# FZZSHAP_REVISED.net
KiCad netlist of a schematic drawn in EAGLE
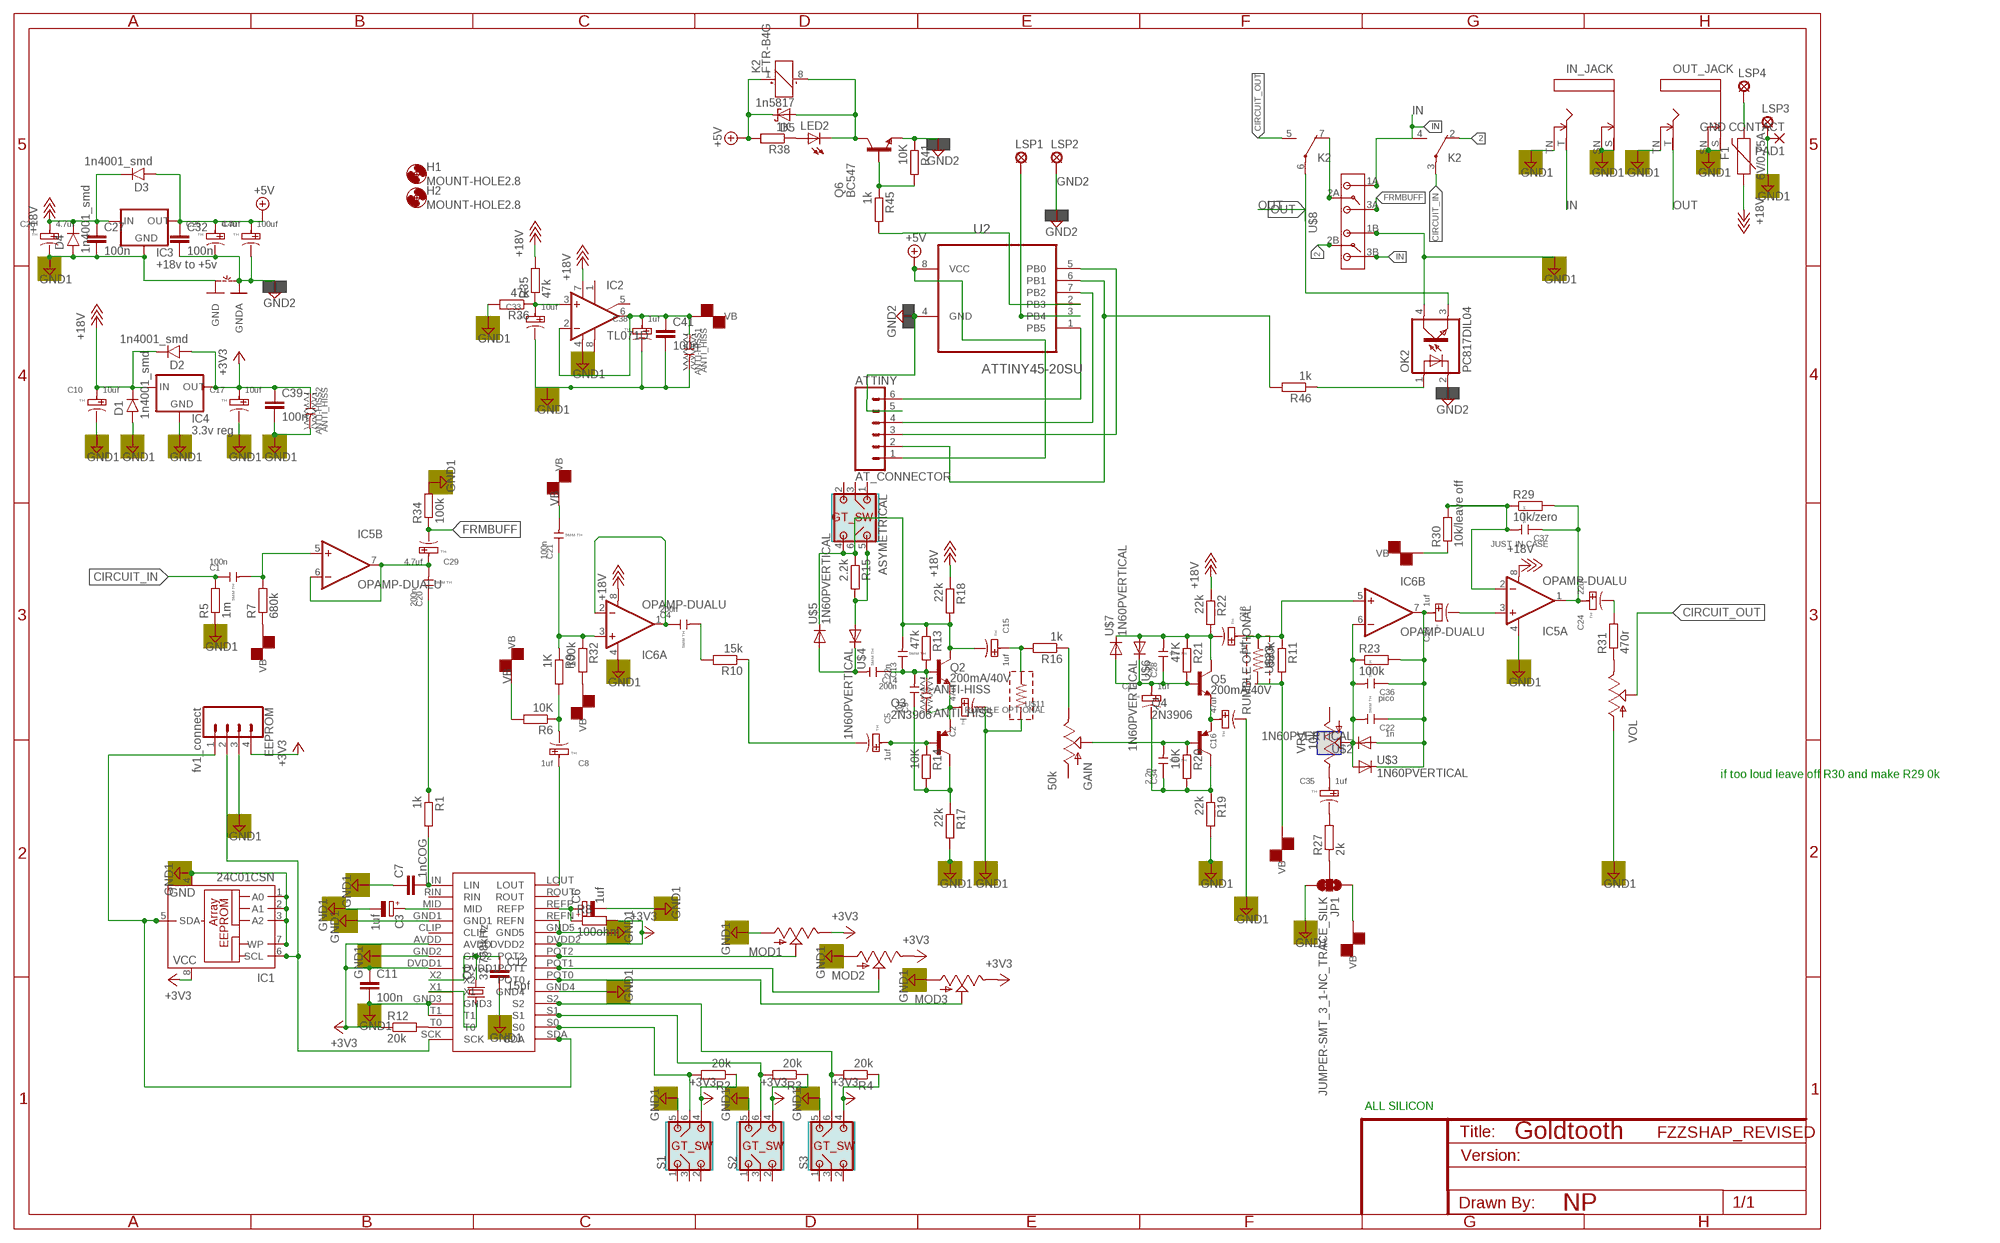
[diagram p0: schematic, sheet 1]

(export (version "E")
  (design (tool "Eeschema 10.0.6"))
  (components
    (comp (ref "ANTI-HISS")
      (value "ANTI_HISS")
      (footprint "eagle-import:SMD_OPTIONAL")
      (libsource (lib "eagle-import") (part "SMDCERAMIC_1206_OPTIONAL"))
    )
    (comp (ref "ANTI-HISS1")
      (value "ANTI_HISS")
      (footprint "eagle-import:SMD_OPTIONAL")
      (libsource (lib "eagle-import") (part "SMDCERAMIC_1206_OPTIONAL"))
    )
    (comp (ref "ANTI-HISS2")
      (value "ANTI_HISS")
      (footprint "eagle-import:SMD_OPTIONAL")
      (libsource (lib "eagle-import") (part "SMDCERAMIC_1206_OPTIONAL"))
    )
    (comp (ref "ASYMETRICAL")
      (value "DP03SWPOT")
      (footprint "eagle-import:DP-03")
      (libsource (lib "eagle-import") (part "DP03SWPOT"))
    )
    (comp (ref "ATTINY")
      (value "AT_CONNECTOR")
      (footprint "eagle-import:1X06_LONGPADS")
      (libsource (lib "eagle-import") (part "CONN_06LONGPADS"))
    )
    (comp (ref "C1")
      (value "100n")
      (footprint "eagle-import:CERAMIC-5MM")
      (fields (field (name "PACKAGE") "5MM TH"))
      (libsource (lib "eagle-import") (part "THRU_HOLE_5MM_SPACING"))
    )
    (comp (ref "C2")
      (value "47uf")
      (footprint "eagle-import:PC-D5.3MM")
      (fields (field (name "PACKAGE") "TH"))
      (libsource (lib "eagle-import") (part "THRU-HOLE-POLARIZED"))
    )
    (comp (ref "C3")
      (value "1uf")
      (footprint "eagle-import:A_3216-18R")
      (libsource (lib "eagle-import") (part "CPOL-EUA/3216-18R"))
    )
    (comp (ref "C4")
      (value "200n")
      (footprint "eagle-import:CERAMIC-5MM")
      (fields (field (name "PACKAGE") "5MM TH"))
      (libsource (lib "eagle-import") (part "THRU_HOLE_5MM_SPACING"))
    )
    (comp (ref "C5")
      (value "1uf")
      (footprint "eagle-import:PC-D5.3MM")
      (fields (field (name "PACKAGE") "TH"))
      (libsource (lib "eagle-import") (part "THRU-HOLE-POLARIZED"))
    )
    (comp (ref "C6")
      (value "1uf")
      (footprint "eagle-import:A_3216-18R")
      (libsource (lib "eagle-import") (part "CPOL-EUA/3216-18R"))
    )
    (comp (ref "C7")
      (value "1nCOG")
      (footprint "eagle-import:C0805K")
      (libsource (lib "eagle-import") (part "C-EUC0805K"))
    )
    (comp (ref "C8")
      (value "1uf")
      (footprint "eagle-import:PC-D5.3MM")
      (fields (field (name "PACKAGE") "TH"))
      (libsource (lib "eagle-import") (part "THRU-HOLE-POLARIZED"))
    )
    (comp (ref "C9")
      (value "1uf")
      (footprint "eagle-import:CERAMIC-5MM")
      (fields (field (name "PACKAGE") "5MM TH"))
      (libsource (lib "eagle-import") (part "THRU_HOLE_5MM_SPACING"))
    )
    (comp (ref "C10")
      (value "10uf")
      (footprint "eagle-import:PC-D5.3MM")
      (fields (field (name "PACKAGE") "TH"))
      (libsource (lib "eagle-import") (part "THRU-HOLE-POLARIZED"))
    )
    (comp (ref "C11")
      (value "100n")
      (footprint "eagle-import:C0805")
      (libsource (lib "eagle-import") (part "C-EUC0805"))
    )
    (comp (ref "C12")
      (value "15pf")
      (footprint "eagle-import:C0805")
      (libsource (lib "eagle-import") (part "C-EUC0805"))
    )
    (comp (ref "C13")
      (value "22n")
      (footprint "eagle-import:CERAMIC-5MM")
      (fields (field (name "PACKAGE") "5MM TH"))
      (libsource (lib "eagle-import") (part "THRU_HOLE_5MM_SPACING"))
    )
    (comp (ref "C14")
      (value "200n")
      (footprint "eagle-import:CERAMIC-5MM")
      (fields (field (name "PACKAGE") "5MM TH"))
      (libsource (lib "eagle-import") (part "THRU_HOLE_5MM_SPACING"))
    )
    (comp (ref "C15")
      (value "1uf")
      (footprint "eagle-import:PC-D5.3MM")
      (fields (field (name "PACKAGE") "TH"))
      (libsource (lib "eagle-import") (part "THRU-HOLE-POLARIZED"))
    )
    (comp (ref "C16")
      (value "47uf")
      (footprint "eagle-import:PC-D5.3MM")
      (fields (field (name "PACKAGE") "TH"))
      (libsource (lib "eagle-import") (part "THRU-HOLE-POLARIZED"))
    )
    (comp (ref "C17")
      (value "10uf")
      (footprint "eagle-import:PC-D5.3MM")
      (fields (field (name "PACKAGE") "TH"))
      (libsource (lib "eagle-import") (part "THRU-HOLE-POLARIZED"))
    )
    (comp (ref "C18")
      (value "1uf")
      (footprint "eagle-import:PC-D5.3MM")
      (fields (field (name "PACKAGE") "TH"))
      (libsource (lib "eagle-import") (part "THRU-HOLE-POLARIZED"))
    )
    (comp (ref "C19")
      (value "1uf")
      (footprint "eagle-import:PC-D5.3MM")
      (fields (field (name "PACKAGE") "TH"))
      (libsource (lib "eagle-import") (part "THRU-HOLE-POLARIZED"))
    )
    (comp (ref "C20")
      (value "200n")
      (footprint "eagle-import:CERAMIC-5MM")
      (fields (field (name "PACKAGE") "5MM TH"))
      (libsource (lib "eagle-import") (part "THRU_HOLE_5MM_SPACING"))
    )
    (comp (ref "C21")
      (value "100n")
      (footprint "eagle-import:CERAMIC-5MM")
      (fields (field (name "PACKAGE") "5MM TH"))
      (libsource (lib "eagle-import") (part "THRU_HOLE_5MM_SPACING"))
    )
    (comp (ref "C22")
      (value "1n")
      (footprint "eagle-import:CERAMIC-5MM")
      (fields (field (name "PACKAGE") "5MM TH"))
      (libsource (lib "eagle-import") (part "THRU_HOLE_5MM_SPACING"))
    )
    (comp (ref "C23")
      (value "1uf")
      (footprint "eagle-import:PC-D5.3MM")
      (fields (field (name "PACKAGE") "TH"))
      (libsource (lib "eagle-import") (part "THRU-HOLE-POLARIZED"))
    )
    (comp (ref "C24")
      (value "22uf")
      (footprint "eagle-import:PC-D5.3MM")
      (fields (field (name "PACKAGE") "TH"))
      (libsource (lib "eagle-import") (part "THRU-HOLE-POLARIZED"))
    )
    (comp (ref "C25")
      (value "4.7uf")
      (footprint "eagle-import:PC-D5.3MM")
      (fields (field (name "PACKAGE") "TH"))
      (libsource (lib "eagle-import") (part "THRU-HOLE-POLARIZED"))
    )
    (comp (ref "C26")
      (value "4.7uf")
      (footprint "eagle-import:PC-D5.3MM")
      (fields (field (name "PACKAGE") "TH"))
      (libsource (lib "eagle-import") (part "THRU-HOLE-POLARIZED"))
    )
    (comp (ref "C27")
      (value "100n")
      (footprint "eagle-import:C1206")
      (libsource (lib "eagle-import") (part "resistor_348_C-EUC1206"))
    )
    (comp (ref "C28")
      (value "2.2n")
      (footprint "eagle-import:CERAMIC-5MM")
      (fields (field (name "PACKAGE") "5MM TH"))
      (libsource (lib "eagle-import") (part "THRU_HOLE_5MM_SPACING"))
    )
    (comp (ref "C29")
      (value "4.7uf")
      (footprint "eagle-import:PC-D5.3MM")
      (fields (field (name "PACKAGE") "TH"))
      (libsource (lib "eagle-import") (part "THRU-HOLE-POLARIZED"))
    )
    (comp (ref "C32")
      (value "100n")
      (footprint "eagle-import:C1206")
      (libsource (lib "eagle-import") (part "resistor_348_C-EUC1206"))
    )
    (comp (ref "C33")
      (value "10uf")
      (footprint "eagle-import:PC-D5.3MM")
      (fields (field (name "PACKAGE") "TH"))
      (libsource (lib "eagle-import") (part "THRU-HOLE-POLARIZED"))
    )
    (comp (ref "C34")
      (value "2.2n")
      (footprint "eagle-import:CERAMIC-5MM")
      (fields (field (name "PACKAGE") "5MM TH"))
      (libsource (lib "eagle-import") (part "THRU_HOLE_5MM_SPACING"))
    )
    (comp (ref "C35")
      (value "1uf")
      (footprint "eagle-import:PC-D5.3MM")
      (fields (field (name "PACKAGE") "TH"))
      (libsource (lib "eagle-import") (part "THRU-HOLE-POLARIZED"))
    )
    (comp (ref "C36")
      (value "pico")
      (footprint "eagle-import:CERAMIC-5MM")
      (fields (field (name "PACKAGE") "5MM TH"))
      (libsource (lib "eagle-import") (part "THRU_HOLE_5MM_SPACING"))
    )
    (comp (ref "C37")
      (value "JUST IN CASE")
      (footprint "eagle-import:CERAMIC-5MM")
      (fields (field (name "PACKAGE") "5MM TH"))
      (libsource (lib "eagle-import") (part "THRU_HOLE_5MM_SPACING"))
    )
    (comp (ref "C38")
      (value "1uf")
      (footprint "eagle-import:PC-D5.3MM")
      (fields (field (name "PACKAGE") "TH"))
      (libsource (lib "eagle-import") (part "THRU-HOLE-POLARIZED"))
    )
    (comp (ref "C39")
      (value "100n")
      (footprint "eagle-import:C1206")
      (libsource (lib "eagle-import") (part "resistor_348_C-EUC1206"))
    )
    (comp (ref "C40")
      (value "100uf")
      (footprint "eagle-import:PC-D5.3MM")
      (fields (field (name "PACKAGE") "TH"))
      (libsource (lib "eagle-import") (part "THRU-HOLE-POLARIZED"))
    )
    (comp (ref "C41")
      (value "100n")
      (footprint "eagle-import:C1206")
      (libsource (lib "eagle-import") (part "resistor_348_C-EUC1206"))
    )
    (comp (ref "D1")
      (value "1n4001_smd")
      (footprint "eagle-import:DO41-1")
      (libsource (lib "eagle-import") (part "1N400X.1"))
    )
    (comp (ref "D2")
      (value "1n4001_smd")
      (footprint "eagle-import:DO41-1")
      (libsource (lib "eagle-import") (part "1N400X.1"))
    )
    (comp (ref "D3")
      (value "1n4001_smd")
      (footprint "eagle-import:DO41-1")
      (libsource (lib "eagle-import") (part "1N400X.1"))
    )
    (comp (ref "D4")
      (value "1n4001_smd")
      (footprint "eagle-import:DO41-1")
      (libsource (lib "eagle-import") (part "1N400X.1"))
    )
    (comp (ref "D5")
      (value "1n5817")
      (footprint "eagle-import:SMB")
      (libsource (lib "eagle-import") (part "SCHOTTKY-DIODESMD"))
    )
    (comp (ref "EEPROM")
      (value "fv1_connect")
      (footprint "eagle-import:1X04_LONGPADS")
      (libsource (lib "eagle-import") (part "CONN_04LONGPADS"))
    )
    (comp (ref "F1")
      (value "6V/0.75A")
      (footprint "eagle-import:1206")
      (libsource (lib "eagle-import") (part "PPTC_THREE-QUARTER-AMP"))
    )
    (comp (ref "GAIN")
      (value "50k")
      (footprint "eagle-import:SLIDER_PAC")
      (libsource (lib "eagle-import") (part "POTSLIDEY"))
    )
    (comp (ref "H1")
      (value "MOUNT-HOLE2.8")
      (footprint "eagle-import:2,8")
      (libsource (lib "eagle-import") (part "MOUNT-HOLE2.8"))
    )
    (comp (ref "H2")
      (value "MOUNT-HOLE2.8")
      (footprint "eagle-import:2,8")
      (libsource (lib "eagle-import") (part "MOUNT-HOLE2.8"))
    )
    (comp (ref "IC1")
      (value "24C01CSN")
      (footprint "eagle-import:SO-08")
      (fields (field (name "MF") "MICROCHIP") (field (name "MPN") "24C01C/SN"))
      (libsource (lib "eagle-import") (part "24CSN01C"))
    )
    (comp (ref "IC2")
      (value "TL071D")
      (footprint "eagle-import:SO08")
      (libsource (lib "eagle-import") (part "TL071D"))
    )
    (comp (ref "IC3")
      (value "+18v to +5v")
      (footprint "eagle-import:TO-252")
      (libsource (lib "eagle-import") (part "V_REG_78XX7812"))
    )
    (comp (ref "IC4")
      (value "3.3v reg")
      (footprint "eagle-import:SOT223")
      (libsource (lib "eagle-import") (part "78M33"))
    )
    (comp (ref "IC5")
      (value "OPAMP-DUALU")
      (footprint "eagle-import:SO08")
      (libsource (lib "eagle-import") (part "OPAMP-DUALU"))
    )
    (comp (ref "IC6")
      (value "OPAMP-DUALU")
      (footprint "eagle-import:SO08")
      (libsource (lib "eagle-import") (part "OPAMP-DUALU"))
    )
    (comp (ref "IN_JACK")
      (value "MMMONNN")
      (footprint "eagle-import:MONO")
      (fields (field (name "SPICEPREFIX") "E"))
      (libsource (lib "eagle-import") (part "MMMONNN"))
    )
    (comp (ref "JP1")
      (value "JUMPER-SMT_3_1-NC_TRACE_SILK")
      (footprint "eagle-import:SMT-JUMPER_3_1-NC_TRACE_SILK")
      (libsource (lib "eagle-import") (part "JUMPER-SMT_3_1-NC_TRACE_SILK"))
    )
    (comp (ref "K2")
      (value "FTR-B4G")
      (footprint "eagle-import:FTR-B4G")
      (libsource (lib "eagle-import") (part "FTR-B4G"))
    )
    (comp (ref "LED2")
      (value "LED3MM")
      (footprint "eagle-import:LED3MM")
      (libsource (lib "eagle-import") (part "LED3MM"))
    )
    (comp (ref "LSP1")
      (value "LSP10")
      (footprint "eagle-import:LSP10")
      (libsource (lib "eagle-import") (part "LSP10"))
    )
    (comp (ref "LSP2")
      (value "LSP10")
      (footprint "eagle-import:LSP10")
      (libsource (lib "eagle-import") (part "LSP10"))
    )
    (comp (ref "LSP3")
      (value "LSP10")
      (footprint "eagle-import:LSP10")
      (libsource (lib "eagle-import") (part "LSP10"))
    )
    (comp (ref "LSP4")
      (value "LSP10")
      (footprint "eagle-import:LSP10")
      (libsource (lib "eagle-import") (part "LSP10"))
    )
    (comp (ref "MOD1")
      (value "POTSLIDEY")
      (footprint "eagle-import:SLIDER_PAC")
      (libsource (lib "eagle-import") (part "POTSLIDEY"))
    )
    (comp (ref "MOD2")
      (value "POTSLIDEY")
      (footprint "eagle-import:SLIDER_PAC")
      (libsource (lib "eagle-import") (part "POTSLIDEY"))
    )
    (comp (ref "MOD3")
      (value "POTSLIDEY")
      (footprint "eagle-import:SLIDER_PAC")
      (libsource (lib "eagle-import") (part "POTSLIDEY"))
    )
    (comp (ref "OK2")
      (value "PC817DIL04")
      (footprint "eagle-import:SMD4")
      (libsource (lib "eagle-import") (part "PC817DIL04"))
    )
    (comp (ref "OUT_JACK")
      (value "MMMONNN")
      (footprint "eagle-import:MONO")
      (libsource (lib "eagle-import") (part "MMMONNN"))
    )
    (comp (ref "PAD1")
      (value "GND CONTACT")
      (footprint "eagle-import:SMD2,54-5,08")
      (libsource (lib "eagle-import") (part "SMD5"))
    )
    (comp (ref "Q1")
      (value "32.768kHz")
      (footprint "eagle-import:CRYSTAL-TXC-7A")
      (libsource (lib "eagle-import") (part "CRYSTALTXC-7A"))
    )
    (comp (ref "Q2")
      (value "200mA/40V")
      (footprint "eagle-import:TO-92")
      (libsource (lib "eagle-import") (part "TRANS_NPN-2N3904"))
    )
    (comp (ref "Q3")
      (value "2N3906")
      (footprint "eagle-import:TO92")
      (libsource (lib "eagle-import") (part "2N3906"))
    )
    (comp (ref "Q4")
      (value "2N3906")
      (footprint "eagle-import:TO92")
      (libsource (lib "eagle-import") (part "2N3906"))
    )
    (comp (ref "Q5")
      (value "200mA/40V")
      (footprint "eagle-import:TO-92")
      (libsource (lib "eagle-import") (part "TRANS_NPN-2N3904"))
    )
    (comp (ref "Q6")
      (value "BC547")
      (footprint "eagle-import:TO92")
      (libsource (lib "eagle-import") (part "BC547"))
    )
    (comp (ref "R1")
      (value "1k")
      (footprint "eagle-import:R1206")
      (libsource (lib "eagle-import") (part "R-EU_R1206"))
    )
    (comp (ref "R2")
      (value "20k")
      (footprint "eagle-import:R1206")
      (libsource (lib "eagle-import") (part "R-EU_R1206"))
    )
    (comp (ref "R3")
      (value "20k")
      (footprint "eagle-import:R1206")
      (libsource (lib "eagle-import") (part "R-EU_R1206"))
    )
    (comp (ref "R4")
      (value "20k")
      (footprint "eagle-import:R1206")
      (libsource (lib "eagle-import") (part "R-EU_R1206"))
    )
    (comp (ref "R5")
      (value "1m")
      (footprint "eagle-import:R1206")
      (libsource (lib "eagle-import") (part "resistor_348_R-EU_R1206"))
    )
    (comp (ref "R6")
      (value "10K")
      (footprint "eagle-import:R1206")
      (libsource (lib "eagle-import") (part "resistor_348_R-EU_R1206"))
    )
    (comp (ref "R7")
      (value "680k")
      (footprint "eagle-import:R1206")
      (libsource (lib "eagle-import") (part "resistor_348_R-EU_R1206"))
    )
    (comp (ref "R8")
      (value "100ohm")
      (footprint "eagle-import:R1206")
      (libsource (lib "eagle-import") (part "R-EU_R1206"))
    )
    (comp (ref "R9")
      (value "1K")
      (footprint "eagle-import:R1206")
      (libsource (lib "eagle-import") (part "resistor_348_R-EU_R1206"))
    )
    (comp (ref "R10")
      (value "15k")
      (footprint "eagle-import:R1206")
      (libsource (lib "eagle-import") (part "resistor_348_R-EU_R1206"))
    )
    (comp (ref "R11")
      (value "680k")
      (footprint "eagle-import:R1206")
      (libsource (lib "eagle-import") (part "resistor_348_R-EU_R1206"))
    )
    (comp (ref "R12")
      (value "20k")
      (footprint "eagle-import:R1206")
      (libsource (lib "eagle-import") (part "R-EU_R1206"))
    )
    (comp (ref "R13")
      (value "47k")
      (footprint "eagle-import:R1206")
      (libsource (lib "eagle-import") (part "resistor_348_R-EU_R1206"))
    )
    (comp (ref "R14")
      (value "10K")
      (footprint "eagle-import:R1206")
      (libsource (lib "eagle-import") (part "resistor_348_R-EU_R1206"))
    )
    (comp (ref "R15")
      (value "2.2k")
      (footprint "eagle-import:R1206")
      (libsource (lib "eagle-import") (part "resistor_348_R-EU_R1206"))
    )
    (comp (ref "R16")
      (value "1k")
      (footprint "eagle-import:R1206")
      (libsource (lib "eagle-import") (part "resistor_348_R-EU_R1206"))
    )
    (comp (ref "R17")
      (value "22k")
      (footprint "eagle-import:R1206")
      (libsource (lib "eagle-import") (part "resistor_348_R-EU_R1206"))
    )
    (comp (ref "R18")
      (value "22k")
      (footprint "eagle-import:R1206")
      (libsource (lib "eagle-import") (part "resistor_348_R-EU_R1206"))
    )
    (comp (ref "R19")
      (value "22k")
      (footprint "eagle-import:R1206")
      (libsource (lib "eagle-import") (part "resistor_348_R-EU_R1206"))
    )
    (comp (ref "R20")
      (value "10K")
      (footprint "eagle-import:R1206")
      (libsource (lib "eagle-import") (part "resistor_348_R-EU_R1206"))
    )
    (comp (ref "R21")
      (value "47K")
      (footprint "eagle-import:R1206")
      (libsource (lib "eagle-import") (part "resistor_348_R-EU_R1206"))
    )
    (comp (ref "R22")
      (value "22k")
      (footprint "eagle-import:R1206")
      (libsource (lib "eagle-import") (part "resistor_348_R-EU_R1206"))
    )
    (comp (ref "R23")
      (value "100k")
      (footprint "eagle-import:R1206")
      (libsource (lib "eagle-import") (part "resistor_348_R-EU_R1206"))
    )
    (comp (ref "R27")
      (value "2k")
      (footprint "eagle-import:R1206")
      (libsource (lib "eagle-import") (part "resistor_348_R-EU_R1206"))
    )
    (comp (ref "R29")
      (value "10k/zero")
      (footprint "eagle-import:R1206")
      (libsource (lib "eagle-import") (part "resistor_348_R-EU_R1206"))
    )
    (comp (ref "R30")
      (value "10k/leave off")
      (footprint "eagle-import:R1206")
      (libsource (lib "eagle-import") (part "resistor_348_R-EU_R1206"))
    )
    (comp (ref "R31")
      (value "470r")
      (footprint "eagle-import:R1206")
      (libsource (lib "eagle-import") (part "resistor_348_R-EU_R1206"))
    )
    (comp (ref "R32")
      (value "100k")
      (footprint "eagle-import:R1206")
      (libsource (lib "eagle-import") (part "resistor_348_R-EU_R1206"))
    )
    (comp (ref "R34")
      (value "100k")
      (footprint "eagle-import:R1206")
      (libsource (lib "eagle-import") (part "resistor_348_R-EU_R1206"))
    )
    (comp (ref "R35")
      (value "47k")
      (footprint "eagle-import:R1206")
      (libsource (lib "eagle-import") (part "resistor_348_R-EU_R1206"))
    )
    (comp (ref "R36")
      (value "47k")
      (footprint "eagle-import:R1206")
      (libsource (lib "eagle-import") (part "resistor_348_R-EU_R1206"))
    )
    (comp (ref "R38")
      (value "1K")
      (footprint "eagle-import:M1206")
      (libsource (lib "eagle-import") (part "resistor_348_R-EU_M1206"))
    )
    (comp (ref "R41")
      (value "10K")
      (footprint "eagle-import:M1206")
      (libsource (lib "eagle-import") (part "resistor_348_R-EU_M1206"))
    )
    (comp (ref "R45")
      (value "1k")
      (footprint "eagle-import:M1206")
      (libsource (lib "eagle-import") (part "resistor_348_R-EU_M1206"))
    )
    (comp (ref "R46")
      (value "1k")
      (footprint "eagle-import:M1206")
      (libsource (lib "eagle-import") (part "resistor_348_R-EU_M1206"))
    )
    (comp (ref "S1")
      (value "DP03SWPOT")
      (footprint "eagle-import:DP-03")
      (libsource (lib "eagle-import") (part "DP03SWPOT"))
    )
    (comp (ref "S2")
      (value "DP03SWPOT")
      (footprint "eagle-import:DP-03")
      (libsource (lib "eagle-import") (part "DP03SWPOT"))
    )
    (comp (ref "S3")
      (value "DP03SWPOT")
      (footprint "eagle-import:DP-03")
      (libsource (lib "eagle-import") (part "DP03SWPOT"))
    )
    (comp (ref "U$1")
      (value "FV-1SOIC28")
      (footprint "eagle-import:SOIC28")
      (libsource (lib "eagle-import") (part "FV-1SOIC28"))
    )
    (comp (ref "U$2")
      (value "1N60PVERTICAL")
      (footprint "eagle-import:DO41-1")
      (libsource (lib "eagle-import") (part "1N60PVERTICAL"))
    )
    (comp (ref "U$3")
      (value "1N60PVERTICAL")
      (footprint "eagle-import:DO41-1")
      (libsource (lib "eagle-import") (part "1N60PVERTICAL"))
    )
    (comp (ref "U$4")
      (value "1N60PVERTICAL")
      (footprint "eagle-import:DO41-1")
      (libsource (lib "eagle-import") (part "1N60PVERTICAL"))
    )
    (comp (ref "U$5")
      (value "1N60PVERTICAL")
      (footprint "eagle-import:DO41-1")
      (libsource (lib "eagle-import") (part "1N60PVERTICAL"))
    )
    (comp (ref "U$6")
      (value "1N60PVERTICAL")
      (footprint "eagle-import:DO41-1")
      (libsource (lib "eagle-import") (part "1N60PVERTICAL"))
    )
    (comp (ref "U$7")
      (value "1N60PVERTICAL")
      (footprint "eagle-import:DO41-1")
      (libsource (lib "eagle-import") (part "1N60PVERTICAL"))
    )
    (comp (ref "U$8")
      (value "BYSWITCH")
      (footprint "eagle-import:BUFF_TRBYPASS")
      (libsource (lib "eagle-import") (part "BYSWITCH"))
    )
    (comp (ref "U$11")
      (value "RUMBLE OPTIONAL")
      (footprint "eagle-import:C1206")
      (libsource (lib "eagle-import") (part "SMD_TOPTIONAL_RESISTOR_1206"))
    )
    (comp (ref "U$23")
      (value "RUMBLE OPTIONAL")
      (footprint "eagle-import:C1206")
      (libsource (lib "eagle-import") (part "SMD_TOPTIONAL_RESISTOR_1206"))
    )
    (comp (ref "U2")
      (value "ATTINY45-20SU")
      (footprint "eagle-import:SOIC127P798X216-8N")
      (libsource (lib "eagle-import") (part "ATTINY45-20SU"))
    )
    (comp (ref "VOL")
      (value "POTSLIDEY")
      (footprint "eagle-import:SLIDER_PAC")
      (libsource (lib "eagle-import") (part "POTSLIDEY"))
    )
    (comp (ref "VR1")
      (value "10k")
      (footprint "eagle-import:3223G")
      (libsource (lib "eagle-import") (part "TRIM_US-3223G"))
    )
    (comp (ref "~NUDEV~1")
      (value "GND-GNDA1,27MM")
      (footprint "eagle-import:GND-GNDA-1,27MM")
      (libsource (lib "eagle-import") (part "GND-GNDA1,27MM"))
    )
  )
  (nets
    (net (code "1") (name "+3V3") (class "Default")
      (node (ref "ANTI-HISS2") (pin "1") (pinfunction "1_1") (pintype "passive"))
      (node (ref "C11") (pin "1") (pinfunction "1_1") (pintype "passive"))
      (node (ref "C17") (pin "+") (pinfunction "+_+") (pintype "passive"))
      (node (ref "C39") (pin "1") (pinfunction "1_1") (pintype "passive"))
      (node (ref "D2") (pin "A") (pinfunction "A_A") (pintype "passive"))
      (node (ref "EEPROM") (pin "4") (pinfunction "4_4") (pintype "passive"))
      (node (ref "IC1") (pin "8") (pinfunction "VCC_8") (pintype "power_in"))
      (node (ref "IC4") (pin "3") (pinfunction "OUT_3") (pintype "passive"))
      (node (ref "MOD1") (pin "3") (pinfunction "E_3") (pintype "passive"))
      (node (ref "MOD2") (pin "3") (pinfunction "E_3") (pintype "passive"))
      (node (ref "MOD3") (pin "3") (pinfunction "E_3") (pintype "passive"))
      (node (ref "R12") (pin "1") (pinfunction "1_1") (pintype "passive"))
      (node (ref "R2") (pin "1") (pinfunction "1_1") (pintype "passive"))
      (node (ref "R3") (pin "1") (pinfunction "1_1") (pintype "passive"))
      (node (ref "R4") (pin "1") (pinfunction "1_1") (pintype "passive"))
      (node (ref "R8") (pin "2") (pinfunction "2_2") (pintype "passive"))
      (node (ref "S1") (pin "4") (pinfunction "4_4") (pintype "passive"))
      (node (ref "S2") (pin "4") (pinfunction "4_4") (pintype "passive"))
      (node (ref "S3") (pin "4") (pinfunction "4_4") (pintype "passive"))
      (node (ref "U$1") (pin "AVDD") (pinfunction "AVDD_AVDD") (pintype "power_in"))
      (node (ref "U$1") (pin "DVDD1") (pinfunction "DVDD1_DVDD1") (pintype "power_in"))
      (node (ref "U$1") (pin "DVDD2") (pinfunction "DVDD2_DVDD2") (pintype "power_in"))
    )
    (net (code "2") (name "+5V") (class "Default")
      (node (ref "ATTINY") (pin "1") (pinfunction "1_1") (pintype "passive"))
      (node (ref "C25") (pin "+") (pinfunction "+_+") (pintype "passive"))
      (node (ref "C32") (pin "1") (pinfunction "1_1") (pintype "passive"))
      (node (ref "C40") (pin "+") (pinfunction "+_+") (pintype "passive"))
      (node (ref "D3") (pin "A") (pinfunction "A_A") (pintype "passive"))
      (node (ref "D5") (pin "C") (pinfunction "C_C") (pintype "passive"))
      (node (ref "IC3") (pin "2") (pinfunction "OUT_2") (pintype "passive"))
      (node (ref "K2") (pin "1") (pinfunction "+_1") (pintype "passive"))
      (node (ref "R38") (pin "2") (pinfunction "2_2") (pintype "passive"))
      (node (ref "U2") (pin "8") (pinfunction "VCC_8") (pintype "power_in"))
    )
    (net (code "3") (name "+18V") (class "Default")
      (node (ref "C10") (pin "+") (pinfunction "+_+") (pintype "passive"))
      (node (ref "C26") (pin "+") (pinfunction "+_+") (pintype "passive"))
      (node (ref "C27") (pin "1") (pinfunction "1_1") (pintype "passive"))
      (node (ref "D1") (pin "C") (pinfunction "C_C") (pintype "passive"))
      (node (ref "D2") (pin "C") (pinfunction "C_C") (pintype "passive"))
      (node (ref "D3") (pin "C") (pinfunction "C_C") (pintype "passive"))
      (node (ref "D4") (pin "C") (pinfunction "C_C") (pintype "passive"))
      (node (ref "F1") (pin "1") (pinfunction "1_1") (pintype "bidirectional"))
      (node (ref "IC2") (pin "7") (pinfunction "V+_7") (pintype "power_in"))
      (node (ref "IC3") (pin "1") (pinfunction "IN_1") (pintype "input"))
      (node (ref "IC4") (pin "1") (pinfunction "IN_1") (pintype "input"))
      (node (ref "IC5") (pin "8") (pinfunction "V+_8") (pintype "power_in"))
      (node (ref "IC6") (pin "8") (pinfunction "V+_8") (pintype "power_in"))
      (node (ref "R18") (pin "1") (pinfunction "1_1") (pintype "passive"))
      (node (ref "R22") (pin "1") (pinfunction "1_1") (pintype "passive"))
      (node (ref "R35") (pin "2") (pinfunction "2_2") (pintype "passive"))
    )
    (net (code "4") (name "2") (class "Default")
      (node (ref "K2") (pin "2") (pinfunction "O_2") (pintype "passive"))
      (node (ref "U$8") (pin "2B") (pinfunction "2B_2B") (pintype "passive"))
    )
    (net (code "5") (name "CIRCUIT_IN") (class "Default")
      (node (ref "C1") (pin "1") (pinfunction "1_1") (pintype "passive"))
      (node (ref "K2") (pin "3") (pinfunction "P_3") (pintype "passive"))
      (node (ref "R5") (pin "2") (pinfunction "2_2") (pintype "passive"))
    )
    (net (code "6") (name "CIRCUIT_OUT") (class "Default")
      (node (ref "K2") (pin "5") (pinfunction "S_5") (pintype "passive"))
      (node (ref "VOL") (pin "2") (pinfunction "S_2") (pintype "passive"))
    )
    (net (code "7") (name "FRMBUFF") (class "Default")
      (node (ref "C29") (pin "-") (pinfunction "-_-") (pintype "passive"))
      (node (ref "R34") (pin "1") (pinfunction "1_1") (pintype "passive"))
      (node (ref "U$8") (pin "3A") (pinfunction "3A_3A") (pintype "passive"))
    )
    (net (code "8") (name "GND1") (class "Default")
      (node (ref "ANTI-HISS1") (pin "2") (pinfunction "2_2") (pintype "passive"))
      (node (ref "ANTI-HISS2") (pin "2") (pinfunction "2_2") (pintype "passive"))
      (node (ref "C10") (pin "-") (pinfunction "-_-") (pintype "passive"))
      (node (ref "C11") (pin "2") (pinfunction "2_2") (pintype "passive"))
      (node (ref "C12") (pin "2") (pinfunction "2_2") (pintype "passive"))
      (node (ref "C16") (pin "-") (pinfunction "-_-") (pintype "passive"))
      (node (ref "C17") (pin "-") (pinfunction "-_-") (pintype "passive"))
      (node (ref "C2") (pin "-") (pinfunction "-_-") (pintype "passive"))
      (node (ref "C26") (pin "-") (pinfunction "-_-") (pintype "passive"))
      (node (ref "C27") (pin "2") (pinfunction "2_2") (pintype "passive"))
      (node (ref "C3") (pin "-") (pinfunction "-_-") (pintype "passive"))
      (node (ref "C33") (pin "-") (pinfunction "-_-") (pintype "passive"))
      (node (ref "C38") (pin "-") (pinfunction "-_-") (pintype "passive"))
      (node (ref "C39") (pin "2") (pinfunction "2_2") (pintype "passive"))
      (node (ref "C41") (pin "2") (pinfunction "2_2") (pintype "passive"))
      (node (ref "C6") (pin "-") (pinfunction "-_-") (pintype "passive"))
      (node (ref "C7") (pin "1") (pinfunction "1_1") (pintype "passive"))
      (node (ref "D1") (pin "A") (pinfunction "A_A") (pintype "passive"))
      (node (ref "D4") (pin "A") (pinfunction "A_A") (pintype "passive"))
      (node (ref "EEPROM") (pin "3") (pinfunction "3_3") (pintype "passive"))
      (node (ref "IC1") (pin "1") (pinfunction "A0_1") (pintype "input"))
      (node (ref "IC1") (pin "2") (pinfunction "A1_2") (pintype "input"))
      (node (ref "IC1") (pin "3") (pinfunction "A2_3") (pintype "input"))
      (node (ref "IC1") (pin "4") (pinfunction "GND_4") (pintype "power_in"))
      (node (ref "IC1") (pin "7") (pinfunction "WP_7") (pintype "input"))
      (node (ref "IC2") (pin "4") (pinfunction "V-_4") (pintype "power_in"))
      (node (ref "IC3") (pin "3") (pinfunction "GND_3") (pintype "input"))
      (node (ref "IC4") (pin "2") (pinfunction "GND_2") (pintype "input"))
      (node (ref "IC4") (pin "4") (pinfunction "GND_4") (pintype "input"))
      (node (ref "IC5") (pin "4") (pinfunction "V-_4") (pintype "power_in"))
      (node (ref "IC6") (pin "4") (pinfunction "V-_4") (pintype "power_in"))
      (node (ref "IN_JACK") (pin "S") (pinfunction "S_S") (pintype "passive"))
      (node (ref "IN_JACK") (pin "SN") (pinfunction "SN_SN") (pintype "passive"))
      (node (ref "IN_JACK") (pin "TN") (pinfunction "TN_TN") (pintype "passive"))
      (node (ref "JP1") (pin "3") (pinfunction "3_3") (pintype "passive"))
      (node (ref "LSP3") (pin "MP") (pinfunction "MP_MP") (pintype "passive"))
      (node (ref "MOD1") (pin "1") (pinfunction "A_1") (pintype "passive"))
      (node (ref "MOD2") (pin "1") (pinfunction "A_1") (pintype "passive"))
      (node (ref "MOD3") (pin "1") (pinfunction "A_1") (pintype "passive"))
      (node (ref "OK2") (pin "4") (pinfunction "COL_4") (pintype "passive"))
      (node (ref "OUT_JACK") (pin "S") (pinfunction "S_S") (pintype "passive"))
      (node (ref "OUT_JACK") (pin "SN") (pinfunction "SN_SN") (pintype "passive"))
      (node (ref "OUT_JACK") (pin "TN") (pinfunction "TN_TN") (pintype "passive"))
      (node (ref "PAD1") (pin "1") (pinfunction "P_1") (pintype "passive"))
      (node (ref "R17") (pin "2") (pinfunction "2_2") (pintype "passive"))
      (node (ref "R19") (pin "2") (pinfunction "2_2") (pintype "passive"))
      (node (ref "R34") (pin "2") (pinfunction "2_2") (pintype "passive"))
      (node (ref "R36") (pin "2") (pinfunction "2_2") (pintype "passive"))
      (node (ref "R5") (pin "1") (pinfunction "1_1") (pintype "passive"))
      (node (ref "S1") (pin "5") (pinfunction "6_5") (pintype "passive"))
      (node (ref "S2") (pin "5") (pinfunction "6_5") (pintype "passive"))
      (node (ref "S3") (pin "5") (pinfunction "6_5") (pintype "passive"))
      (node (ref "U$1") (pin "GND1") (pinfunction "GND1_GND1") (pintype "power_in"))
      (node (ref "U$1") (pin "GND2") (pinfunction "GND2_GND2") (pintype "power_in"))
      (node (ref "U$1") (pin "GND3") (pinfunction "GND3_GND3") (pintype "power_in"))
      (node (ref "U$1") (pin "GND4") (pinfunction "GND4_GND4") (pintype "power_in"))
      (node (ref "U$1") (pin "GND5") (pinfunction "GND5_GND5") (pintype "power_in"))
      (node (ref "U$1") (pin "REFN") (pinfunction "REFN_REFN") (pintype "input"))
      (node (ref "U$1") (pin "T1") (pinfunction "T1_T1") (pintype "input"))
      (node (ref "U$11") (pin "2") (pinfunction "2_2") (pintype "passive"))
      (node (ref "U$8") (pin "1B") (pinfunction "1B_1B") (pintype "passive"))
      (node (ref "VOL") (pin "1") (pinfunction "A_1") (pintype "passive"))
      (node (ref "~NUDEV~1") (pin "GND") (pinfunction "GND_GND") (pintype "power_in"))
    )
    (net (code "9") (name "GND2") (class "Default")
      (node (ref "ATTINY") (pin "5") (pinfunction "5_5") (pintype "passive"))
      (node (ref "C25") (pin "-") (pinfunction "-_-") (pintype "passive"))
      (node (ref "C32") (pin "2") (pinfunction "2_2") (pintype "passive"))
      (node (ref "C40") (pin "-") (pinfunction "-_-") (pintype "passive"))
      (node (ref "LSP2") (pin "MP") (pinfunction "MP_MP") (pintype "passive"))
      (node (ref "OK2") (pin "2") (pinfunction "C_2") (pintype "passive"))
      (node (ref "Q6") (pin "1") (pinfunction "E_1") (pintype "passive"))
      (node (ref "R41") (pin "1") (pinfunction "1_1") (pintype "passive"))
      (node (ref "U2") (pin "4") (pinfunction "GND_4") (pintype "passive"))
      (node (ref "~NUDEV~1") (pin "GNDA") (pinfunction "GNDA_GNDA") (pintype "power_in"))
    )
    (net (code "10") (name "IN") (class "Default")
      (node (ref "IN_JACK") (pin "T") (pinfunction "T_T") (pintype "passive"))
      (node (ref "K2") (pin "4") (pinfunction "S_4") (pintype "passive"))
      (node (ref "U$8") (pin "1A") (pinfunction "1A_1A") (pintype "passive"))
      (node (ref "U$8") (pin "3B") (pinfunction "3B_3B") (pintype "passive"))
    )
    (net (code "11") (name "Net-(ASYMETRICAL-5)") (class "Default")
      (node (ref "ASYMETRICAL") (pin "4") (pinfunction "4_4") (pintype "passive"))
      (node (ref "ASYMETRICAL") (pin "6") (pinfunction "5_6") (pintype "passive"))
      (node (ref "C13") (pin "2") (pinfunction "2_2") (pintype "passive"))
      (node (ref "C15") (pin "-") (pinfunction "-_-") (pintype "passive"))
      (node (ref "Q2") (pin "3") (pinfunction "C_3") (pintype "passive"))
      (node (ref "R13") (pin "1") (pinfunction "1_1") (pintype "passive"))
      (node (ref "R15") (pin "1") (pinfunction "1_1") (pintype "passive"))
      (node (ref "R18") (pin "2") (pinfunction "2_2") (pintype "passive"))
      (node (ref "U$5") (pin "C") (pinfunction "C_C") (pintype "passive"))
    )
    (net (code "12") (name "Net-(ASYMETRICAL-6)") (class "Default")
      (node (ref "ASYMETRICAL") (pin "5") (pinfunction "6_5") (pintype "passive"))
      (node (ref "R15") (pin "2") (pinfunction "2_2") (pintype "passive"))
      (node (ref "U$4") (pin "A") (pinfunction "A_A") (pintype "passive"))
    )
    (net (code "13") (name "Net-(C3-Pad+)") (class "Default")
      (node (ref "C3") (pin "+") (pinfunction "+_+") (pintype "passive"))
      (node (ref "U$1") (pin "MID") (pinfunction "MID_MID") (pintype "input"))
    )
    (net (code "14") (name "Net-(C4-Pad2)") (class "Default")
      (node (ref "C4") (pin "2") (pinfunction "2_2") (pintype "passive"))
      (node (ref "R10") (pin "2") (pinfunction "2_2") (pintype "passive"))
    )
    (net (code "15") (name "Net-(C5-Pad-)") (class "Default")
      (node (ref "C5") (pin "-") (pinfunction "-_-") (pintype "passive"))
      (node (ref "R10") (pin "1") (pinfunction "1_1") (pintype "passive"))
    )
    (net (code "16") (name "Net-(C6-Pad+)") (class "Default")
      (node (ref "C6") (pin "+") (pinfunction "+_+") (pintype "passive"))
      (node (ref "R8") (pin "1") (pinfunction "1_1") (pintype "passive"))
      (node (ref "U$1") (pin "REFP") (pinfunction "REFP_REFP") (pintype "input"))
    )
    (net (code "17") (name "Net-(C7-Pad2)") (class "Default")
      (node (ref "C7") (pin "2") (pinfunction "2_2") (pintype "passive"))
      (node (ref "R1") (pin "2") (pinfunction "2_2") (pintype "passive"))
      (node (ref "U$1") (pin "LIN") (pinfunction "LIN_LIN") (pintype "input"))
    )
    (net (code "18") (name "Net-(C8-Pad+)") (class "Default")
      (node (ref "C8") (pin "+") (pinfunction "+_+") (pintype "passive"))
      (node (ref "U$1") (pin "LOUT") (pinfunction "LOUT_LOUT") (pintype "output"))
    )
    (net (code "19") (name "Net-(C8-Pad-)") (class "Default")
      (node (ref "C8") (pin "-") (pinfunction "-_-") (pintype "passive"))
      (node (ref "R6") (pin "1") (pinfunction "1_1") (pintype "passive"))
      (node (ref "R9") (pin "2") (pinfunction "2_2") (pintype "passive"))
    )
    (net (code "20") (name "Net-(C14-Pad2)") (class "Default")
      (node (ref "C14") (pin "2") (pinfunction "2_2") (pintype "passive"))
      (node (ref "U$4") (pin "C") (pinfunction "C_C") (pintype "passive"))
      (node (ref "U$5") (pin "A") (pinfunction "A_A") (pintype "passive"))
    )
    (net (code "21") (name "Net-(C15-Pad+)") (class "Default")
      (node (ref "C15") (pin "+") (pinfunction "+_+") (pintype "passive"))
      (node (ref "R16") (pin "2") (pinfunction "2_2") (pintype "passive"))
      (node (ref "U$11") (pin "1") (pinfunction "1_1") (pintype "passive"))
    )
    (net (code "22") (name "Net-(C20-Pad1)") (class "Default")
      (node (ref "C20") (pin "1") (pinfunction "1_1") (pintype "passive"))
      (node (ref "R1") (pin "1") (pinfunction "1_1") (pintype "passive"))
    )
    (net (code "23") (name "Net-(C24-Pad-)") (class "Default")
      (node (ref "C24") (pin "-") (pinfunction "-_-") (pintype "passive"))
      (node (ref "R31") (pin "2") (pinfunction "2_2") (pintype "passive"))
    )
    (net (code "24") (name "Net-(C35-Pad-)") (class "Default")
      (node (ref "C35") (pin "-") (pinfunction "-_-") (pintype "passive"))
      (node (ref "R27") (pin "2") (pinfunction "2_2") (pintype "passive"))
    )
    (net (code "25") (name "Net-(F1-Pad2)") (class "Default")
      (node (ref "F1") (pin "2") (pinfunction "2_2") (pintype "bidirectional"))
      (node (ref "LSP4") (pin "MP") (pinfunction "MP_MP") (pintype "passive"))
    )
    (net (code "26") (name "Net-(GAIN-E)") (class "Default")
      (node (ref "GAIN") (pin "3") (pinfunction "E_3") (pintype "passive"))
      (node (ref "R16") (pin "1") (pinfunction "1_1") (pintype "passive"))
    )
    (net (code "27") (name "Net-(GAIN-S)") (class "Default")
      (node (ref "C34") (pin "2") (pinfunction "2_2") (pintype "passive"))
      (node (ref "GAIN") (pin "2") (pinfunction "S_2") (pintype "passive"))
      (node (ref "Q4") (pin "2") (pinfunction "B_2") (pintype "passive"))
      (node (ref "R20") (pin "1") (pinfunction "1_1") (pintype "passive"))
    )
    (net (code "28") (name "Net-(IC1-SCL)") (class "Default")
      (node (ref "EEPROM") (pin "2") (pinfunction "2_2") (pintype "passive"))
      (node (ref "IC1") (pin "6") (pinfunction "SCL_6") (pintype "input"))
      (node (ref "U$1") (pin "SCK") (pinfunction "SCK_SCK") (pintype "bidirectional"))
    )
    (net (code "29") (name "Net-(IC1-SDA)") (class "Default")
      (node (ref "EEPROM") (pin "1") (pinfunction "1_1") (pintype "passive"))
      (node (ref "IC1") (pin "5") (pinfunction "SDA_5") (pintype "bidirectional"))
      (node (ref "U$1") (pin "SDA") (pinfunction "SDA_SDA") (pintype "bidirectional"))
    )
    (net (code "30") (name "Net-(IC2-+IN)") (class "Default")
      (node (ref "C33") (pin "+") (pinfunction "+_+") (pintype "passive"))
      (node (ref "IC2") (pin "3") (pinfunction "+IN_3") (pintype "input"))
      (node (ref "R35") (pin "1") (pinfunction "1_1") (pintype "passive"))
      (node (ref "R36") (pin "1") (pinfunction "1_1") (pintype "passive"))
    )
    (net (code "31") (name "Net-(IC5A-+IN)") (class "Default")
      (node (ref "C23") (pin "-") (pinfunction "-_-") (pintype "passive"))
      (node (ref "IC5") (pin "3") (pinfunction "+IN_3") (pintype "input"))
    )
    (net (code "32") (name "Net-(IC5A--IN)") (class "Default")
      (node (ref "C37") (pin "2") (pinfunction "2_2") (pintype "passive"))
      (node (ref "IC5") (pin "2") (pinfunction "-IN_2") (pintype "input"))
      (node (ref "R29") (pin "1") (pinfunction "1_1") (pintype "passive"))
      (node (ref "R30") (pin "2") (pinfunction "2_2") (pintype "passive"))
    )
    (net (code "33") (name "Net-(IC5A-OUT)") (class "Default")
      (node (ref "C24") (pin "+") (pinfunction "+_+") (pintype "passive"))
      (node (ref "C37") (pin "1") (pinfunction "1_1") (pintype "passive"))
      (node (ref "IC5") (pin "1") (pinfunction "OUT_1") (pintype "output"))
      (node (ref "R29") (pin "2") (pinfunction "2_2") (pintype "passive"))
    )
    (net (code "34") (name "Net-(IC5B-+IN)") (class "Default")
      (node (ref "C1") (pin "2") (pinfunction "2_2") (pintype "passive"))
      (node (ref "IC5") (pin "5") (pinfunction "+IN_5") (pintype "input"))
      (node (ref "R7") (pin "2") (pinfunction "2_2") (pintype "passive"))
    )
    (net (code "35") (name "Net-(IC5B--IN)") (class "Default")
      (node (ref "C20") (pin "2") (pinfunction "2_2") (pintype "passive"))
      (node (ref "C29") (pin "+") (pinfunction "+_+") (pintype "passive"))
      (node (ref "IC5") (pin "6") (pinfunction "-IN_6") (pintype "input"))
      (node (ref "IC5") (pin "7") (pinfunction "OUT_7") (pintype "output"))
    )
    (net (code "36") (name "Net-(IC6A-+IN)") (class "Default")
      (node (ref "C21") (pin "1") (pinfunction "1_1") (pintype "passive"))
      (node (ref "IC6") (pin "3") (pinfunction "+IN_3") (pintype "input"))
      (node (ref "R32") (pin "1") (pinfunction "1_1") (pintype "passive"))
      (node (ref "R9") (pin "1") (pinfunction "1_1") (pintype "passive"))
    )
    (net (code "37") (name "Net-(IC6A--IN)") (class "Default")
      (node (ref "C4") (pin "1") (pinfunction "1_1") (pintype "passive"))
      (node (ref "IC6") (pin "1") (pinfunction "OUT_1") (pintype "output"))
      (node (ref "IC6") (pin "2") (pinfunction "-IN_2") (pintype "input"))
    )
    (net (code "38") (name "Net-(IC6B-+IN)") (class "Default")
      (node (ref "C18") (pin "+") (pinfunction "+_+") (pintype "passive"))
      (node (ref "IC6") (pin "5") (pinfunction "+IN_5") (pintype "input"))
      (node (ref "R11") (pin "1") (pinfunction "1_1") (pintype "passive"))
      (node (ref "U$23") (pin "1") (pinfunction "1_1") (pintype "passive"))
    )
    (net (code "39") (name "Net-(IC6B--IN)") (class "Default")
      (node (ref "C22") (pin "2") (pinfunction "2_2") (pintype "passive"))
      (node (ref "C36") (pin "2") (pinfunction "2_2") (pintype "passive"))
      (node (ref "IC6") (pin "6") (pinfunction "-IN_6") (pintype "input"))
      (node (ref "R23") (pin "1") (pinfunction "1_1") (pintype "passive"))
      (node (ref "U$2") (pin "C") (pinfunction "C_C") (pintype "passive"))
      (node (ref "U$3") (pin "A") (pinfunction "A_A") (pintype "passive"))
      (node (ref "VR1") (pin "2") (pinfunction "S_2") (pintype "passive"))
    )
    (net (code "40") (name "Net-(IC6B-OUT)") (class "Default")
      (node (ref "C22") (pin "1") (pinfunction "1_1") (pintype "passive"))
      (node (ref "C23") (pin "+") (pinfunction "+_+") (pintype "passive"))
      (node (ref "C36") (pin "1") (pinfunction "1_1") (pintype "passive"))
      (node (ref "IC6") (pin "7") (pinfunction "OUT_7") (pintype "output"))
      (node (ref "R23") (pin "2") (pinfunction "2_2") (pintype "passive"))
      (node (ref "U$2") (pin "A") (pinfunction "A_A") (pintype "passive"))
      (node (ref "U$3") (pin "C") (pinfunction "C_C") (pintype "passive"))
    )
    (net (code "41") (name "Net-(JP1-Pad2)") (class "Default")
      (node (ref "JP1") (pin "2") (pinfunction "2_2") (pintype "passive"))
      (node (ref "R27") (pin "1") (pinfunction "1_1") (pintype "passive"))
    )
    (net (code "42") (name "Net-(K2B-O)") (class "Default")
      (node (ref "K2") (pin "7") (pinfunction "O_7") (pintype "passive"))
      (node (ref "U$8") (pin "2A") (pinfunction "2A_2A") (pintype "passive"))
    )
    (net (code "43") (name "Net-(K2C--)") (class "Default")
      (node (ref "D5") (pin "A") (pinfunction "A_A") (pintype "passive"))
      (node (ref "K2") (pin "8") (pinfunction "-_8") (pintype "passive"))
      (node (ref "LED2") (pin "K") (pinfunction "C_K") (pintype "passive"))
      (node (ref "Q6") (pin "3") (pinfunction "C_3") (pintype "passive"))
    )
    (net (code "44") (name "Net-(LED2-PadA)") (class "Default")
      (node (ref "LED2") (pin "A") (pinfunction "A_A") (pintype "passive"))
      (node (ref "R38") (pin "1") (pinfunction "1_1") (pintype "passive"))
    )
    (net (code "45") (name "Net-(MOD1-S)") (class "Default")
      (node (ref "MOD1") (pin "2") (pinfunction "S_2") (pintype "passive"))
      (node (ref "U$1") (pin "POT2") (pinfunction "POT2_POT2") (pintype "input"))
    )
    (net (code "46") (name "Net-(MOD2-S)") (class "Default")
      (node (ref "MOD2") (pin "2") (pinfunction "S_2") (pintype "passive"))
      (node (ref "U$1") (pin "POT1") (pinfunction "POT1_POT1") (pintype "input"))
    )
    (net (code "47") (name "Net-(MOD3-S)") (class "Default")
      (node (ref "MOD3") (pin "2") (pinfunction "S_2") (pintype "passive"))
      (node (ref "U$1") (pin "POT0") (pinfunction "POT0_POT0") (pintype "input"))
    )
    (net (code "48") (name "Net-(OK2-A)") (class "Default")
      (node (ref "OK2") (pin "1") (pinfunction "A_1") (pintype "passive"))
      (node (ref "R46") (pin "1") (pinfunction "1_1") (pintype "passive"))
    )
    (net (code "49") (name "Net-(Q1-1)") (class "Default")
      (node (ref "Q1") (pin "P$1") (pinfunction "1_P$1") (pintype "passive"))
      (node (ref "U$1") (pin "X1") (pinfunction "X1_X1") (pintype "bidirectional"))
    )
    (net (code "50") (name "Net-(Q1-2)") (class "Default")
      (node (ref "C12") (pin "1") (pinfunction "1_1") (pintype "passive"))
      (node (ref "Q1") (pin "P$2") (pinfunction "2_P$2") (pintype "passive"))
      (node (ref "U$1") (pin "X2") (pinfunction "X2_X2") (pintype "bidirectional"))
    )
    (net (code "51") (name "Net-(Q2-B)") (class "Default")
      (node (ref "ANTI-HISS") (pin "1") (pinfunction "1_1") (pintype "passive"))
      (node (ref "C13") (pin "1") (pinfunction "1_1") (pintype "passive"))
      (node (ref "C14") (pin "1") (pinfunction "1_1") (pintype "passive"))
      (node (ref "C9") (pin "2") (pinfunction "2_2") (pintype "passive"))
      (node (ref "Q2") (pin "2") (pinfunction "B_2") (pintype "passive"))
      (node (ref "R13") (pin "2") (pinfunction "2_2") (pintype "passive"))
    )
    (net (code "52") (name "Net-(Q2-E)") (class "Default")
      (node (ref "ANTI-HISS") (pin "2") (pinfunction "2_2") (pintype "passive"))
      (node (ref "C2") (pin "+") (pinfunction "+_+") (pintype "passive"))
      (node (ref "Q2") (pin "1") (pinfunction "E_1") (pintype "passive"))
      (node (ref "Q3") (pin "3") (pinfunction "E_3") (pintype "passive"))
    )
    (net (code "53") (name "Net-(Q3-B)") (class "Default")
      (node (ref "C5") (pin "+") (pinfunction "+_+") (pintype "passive"))
      (node (ref "Q3") (pin "2") (pinfunction "B_2") (pintype "passive"))
      (node (ref "R14") (pin "1") (pinfunction "1_1") (pintype "passive"))
    )
    (net (code "54") (name "Net-(Q3-C)") (class "Default")
      (node (ref "C9") (pin "1") (pinfunction "1_1") (pintype "passive"))
      (node (ref "Q3") (pin "1") (pinfunction "C_1") (pintype "passive"))
      (node (ref "R14") (pin "2") (pinfunction "2_2") (pintype "passive"))
      (node (ref "R17") (pin "1") (pinfunction "1_1") (pintype "passive"))
    )
    (net (code "55") (name "Net-(Q4-C)") (class "Default")
      (node (ref "C19") (pin "-") (pinfunction "-_-") (pintype "passive"))
      (node (ref "C34") (pin "1") (pinfunction "1_1") (pintype "passive"))
      (node (ref "Q4") (pin "1") (pinfunction "C_1") (pintype "passive"))
      (node (ref "R19") (pin "1") (pinfunction "1_1") (pintype "passive"))
      (node (ref "R20") (pin "2") (pinfunction "2_2") (pintype "passive"))
    )
    (net (code "56") (name "Net-(Q4-E)") (class "Default")
      (node (ref "C16") (pin "+") (pinfunction "+_+") (pintype "passive"))
      (node (ref "Q4") (pin "3") (pinfunction "E_3") (pintype "passive"))
      (node (ref "Q5") (pin "1") (pinfunction "E_1") (pintype "passive"))
    )
    (net (code "57") (name "Net-(Q5-B)") (class "Default")
      (node (ref "C19") (pin "+") (pinfunction "+_+") (pintype "passive"))
      (node (ref "C28") (pin "1") (pinfunction "1_1") (pintype "passive"))
      (node (ref "Q5") (pin "2") (pinfunction "B_2") (pintype "passive"))
      (node (ref "R21") (pin "2") (pinfunction "2_2") (pintype "passive"))
      (node (ref "U$6") (pin "C") (pinfunction "C_C") (pintype "passive"))
      (node (ref "U$7") (pin "A") (pinfunction "A_A") (pintype "passive"))
    )
    (net (code "58") (name "Net-(Q5-C)") (class "Default")
      (node (ref "C18") (pin "-") (pinfunction "-_-") (pintype "passive"))
      (node (ref "C28") (pin "2") (pinfunction "2_2") (pintype "passive"))
      (node (ref "Q5") (pin "3") (pinfunction "C_3") (pintype "passive"))
      (node (ref "R21") (pin "1") (pinfunction "1_1") (pintype "passive"))
      (node (ref "R22") (pin "2") (pinfunction "2_2") (pintype "passive"))
      (node (ref "U$6") (pin "A") (pinfunction "A_A") (pintype "passive"))
      (node (ref "U$7") (pin "C") (pinfunction "C_C") (pintype "passive"))
    )
    (net (code "59") (name "Net-(Q6-B)") (class "Default")
      (node (ref "Q6") (pin "2") (pinfunction "B_2") (pintype "passive"))
      (node (ref "R41") (pin "2") (pinfunction "2_2") (pintype "passive"))
      (node (ref "R45") (pin "1") (pinfunction "1_1") (pintype "passive"))
    )
    (net (code "60") (name "Net-(R12-Pad2)") (class "Default")
      (node (ref "R12") (pin "2") (pinfunction "2_2") (pintype "passive"))
      (node (ref "U$1") (pin "T0") (pinfunction "T0_T0") (pintype "input"))
    )
    (net (code "61") (name "Net-(S1-5)") (class "Default")
      (node (ref "R2") (pin "2") (pinfunction "2_2") (pintype "passive"))
      (node (ref "S1") (pin "6") (pinfunction "5_6") (pintype "passive"))
      (node (ref "U$1") (pin "S0") (pinfunction "S0_S0") (pintype "input"))
    )
    (net (code "62") (name "Net-(S2-5)") (class "Default")
      (node (ref "R3") (pin "2") (pinfunction "2_2") (pintype "passive"))
      (node (ref "S2") (pin "6") (pinfunction "5_6") (pintype "passive"))
      (node (ref "U$1") (pin "S1") (pinfunction "S1_S1") (pintype "input"))
    )
    (net (code "63") (name "Net-(S3-5)") (class "Default")
      (node (ref "R4") (pin "2") (pinfunction "2_2") (pintype "passive"))
      (node (ref "S3") (pin "6") (pinfunction "5_6") (pintype "passive"))
      (node (ref "U$1") (pin "S2") (pinfunction "S2_S2") (pintype "input"))
    )
    (net (code "64") (name "Net-(U2-PB0)") (class "Default")
      (node (ref "ATTINY") (pin "3") (pinfunction "3_3") (pintype "passive"))
      (node (ref "U2") (pin "5") (pinfunction "PB0_5") (pintype "bidirectional"))
    )
    (net (code "65") (name "Net-(U2-PB1)") (class "Default")
      (node (ref "ATTINY") (pin "2") (pinfunction "2_2") (pintype "passive"))
      (node (ref "R46") (pin "2") (pinfunction "2_2") (pintype "passive"))
      (node (ref "U2") (pin "6") (pinfunction "PB1_6") (pintype "bidirectional"))
    )
    (net (code "66") (name "Net-(U2-PB2)") (class "Default")
      (node (ref "ATTINY") (pin "4") (pinfunction "4_4") (pintype "passive"))
      (node (ref "U2") (pin "7") (pinfunction "PB2_7") (pintype "bidirectional"))
    )
    (net (code "67") (name "Net-(U2-PB3)") (class "Default")
      (node (ref "R45") (pin "2") (pinfunction "2_2") (pintype "passive"))
      (node (ref "U2") (pin "2") (pinfunction "PB3_2") (pintype "bidirectional"))
    )
    (net (code "68") (name "Net-(U2-PB4)") (class "Default")
      (node (ref "LSP1") (pin "MP") (pinfunction "MP_MP") (pintype "passive"))
      (node (ref "U2") (pin "3") (pinfunction "PB4_3") (pintype "bidirectional"))
    )
    (net (code "69") (name "Net-(U2-PB5)") (class "Default")
      (node (ref "ATTINY") (pin "6") (pinfunction "6_6") (pintype "passive"))
      (node (ref "U2") (pin "1") (pinfunction "PB5_1") (pintype "bidirectional"))
    )
    (net (code "70") (name "Net-(VOL-E)") (class "Default")
      (node (ref "R31") (pin "1") (pinfunction "1_1") (pintype "passive"))
      (node (ref "VOL") (pin "3") (pinfunction "E_3") (pintype "passive"))
    )
    (net (code "71") (name "Net-(VR1-E)") (class "Default")
      (node (ref "C35") (pin "+") (pinfunction "+_+") (pintype "passive"))
      (node (ref "VR1") (pin "3") (pinfunction "E_3") (pintype "passive"))
    )
    (net (code "72") (name "OUT") (class "Default")
      (node (ref "K2") (pin "6") (pinfunction "P_6") (pintype "passive"))
      (node (ref "OK2") (pin "3") (pinfunction "EMIT_3") (pintype "passive"))
      (node (ref "OUT_JACK") (pin "T") (pinfunction "T_T") (pintype "passive"))
    )
    (net (code "73") (name "VB") (class "Default")
      (node (ref "ANTI-HISS1") (pin "1") (pinfunction "1_1") (pintype "passive"))
      (node (ref "C21") (pin "2") (pinfunction "2_2") (pintype "passive"))
      (node (ref "C38") (pin "+") (pinfunction "+_+") (pintype "passive"))
      (node (ref "C41") (pin "1") (pinfunction "1_1") (pintype "passive"))
      (node (ref "IC2") (pin "2") (pinfunction "-IN_2") (pintype "input"))
      (node (ref "IC2") (pin "6") (pinfunction "OUT_6") (pintype "output"))
      (node (ref "JP1") (pin "1") (pinfunction "1_1") (pintype "passive"))
      (node (ref "R11") (pin "2") (pinfunction "2_2") (pintype "passive"))
      (node (ref "R30") (pin "1") (pinfunction "1_1") (pintype "passive"))
      (node (ref "R32") (pin "2") (pinfunction "2_2") (pintype "passive"))
      (node (ref "R6") (pin "2") (pinfunction "2_2") (pintype "passive"))
      (node (ref "R7") (pin "1") (pinfunction "1_1") (pintype "passive"))
      (node (ref "U$23") (pin "2") (pinfunction "2_2") (pintype "passive"))
    )
    (net (code "74") (name "unconnected-(ASYMETRICAL-2-Pad3)") (class "Default")
      (node (ref "ASYMETRICAL") (pin "3") (pinfunction "2_3") (pintype "passive"))
    )
    (net (code "75") (name "unconnected-(ASYMETRICAL-3-Pad2)") (class "Default")
      (node (ref "ASYMETRICAL") (pin "2") (pinfunction "3_2") (pintype "passive"))
    )
    (net (code "76") (name "unconnected-(ASYMETRICAL-Pad1)") (class "Default")
      (node (ref "ASYMETRICAL") (pin "1") (pinfunction "1_1") (pintype "passive"))
    )
    (net (code "77") (name "unconnected-(GAIN-A-Pad1)") (class "Default")
      (node (ref "GAIN") (pin "1") (pinfunction "A_1") (pintype "passive"))
    )
    (net (code "78") (name "unconnected-(IC2-ON1-Pad1)") (class "Default")
      (node (ref "IC2") (pin "1") (pinfunction "ON1_1") (pintype "passive"))
    )
    (net (code "79") (name "unconnected-(IC2-ON2-Pad5)") (class "Default")
      (node (ref "IC2") (pin "5") (pinfunction "ON2_5") (pintype "passive"))
    )
    (net (code "80") (name "unconnected-(IC2-OPT-Pad8)") (class "Default")
      (node (ref "IC2") (pin "8") (pinfunction "OPT_8") (pintype "passive"))
    )
    (net (code "81") (name "unconnected-(S1-2-Pad3)") (class "Default")
      (node (ref "S1") (pin "3") (pinfunction "2_3") (pintype "passive"))
    )
    (net (code "82") (name "unconnected-(S1-3-Pad2)") (class "Default")
      (node (ref "S1") (pin "2") (pinfunction "3_2") (pintype "passive"))
    )
    (net (code "83") (name "unconnected-(S1-Pad1)") (class "Default")
      (node (ref "S1") (pin "1") (pinfunction "1_1") (pintype "passive"))
    )
    (net (code "84") (name "unconnected-(S2-2-Pad3)") (class "Default")
      (node (ref "S2") (pin "3") (pinfunction "2_3") (pintype "passive"))
    )
    (net (code "85") (name "unconnected-(S2-3-Pad2)") (class "Default")
      (node (ref "S2") (pin "2") (pinfunction "3_2") (pintype "passive"))
    )
    (net (code "86") (name "unconnected-(S2-Pad1)") (class "Default")
      (node (ref "S2") (pin "1") (pinfunction "1_1") (pintype "passive"))
    )
    (net (code "87") (name "unconnected-(S3-2-Pad3)") (class "Default")
      (node (ref "S3") (pin "3") (pinfunction "2_3") (pintype "passive"))
    )
    (net (code "88") (name "unconnected-(S3-3-Pad2)") (class "Default")
      (node (ref "S3") (pin "2") (pinfunction "3_2") (pintype "passive"))
    )
    (net (code "89") (name "unconnected-(S3-Pad1)") (class "Default")
      (node (ref "S3") (pin "1") (pinfunction "1_1") (pintype "passive"))
    )
    (net (code "90") (name "unconnected-(U$1-PadCLIP)") (class "Default")
      (node (ref "U$1") (pin "CLIP") (pinfunction "CLIP_CLIP") (pintype "output"))
    )
    (net (code "91") (name "unconnected-(U$1-PadRIN)") (class "Default")
      (node (ref "U$1") (pin "RIN") (pinfunction "RIN_RIN") (pintype "input"))
    )
    (net (code "92") (name "unconnected-(U$1-PadROUT)") (class "Default")
      (node (ref "U$1") (pin "ROUT") (pinfunction "ROUT_ROUT") (pintype "output"))
    )
    (net (code "93") (name "unconnected-(VR1-A-Pad1)") (class "Default")
      (node (ref "VR1") (pin "1") (pinfunction "A_1") (pintype "passive"))
    )
  )
)
